# Cell_Phone_Module.net
KiCad netlist of a schematic drawn in Altium Designer
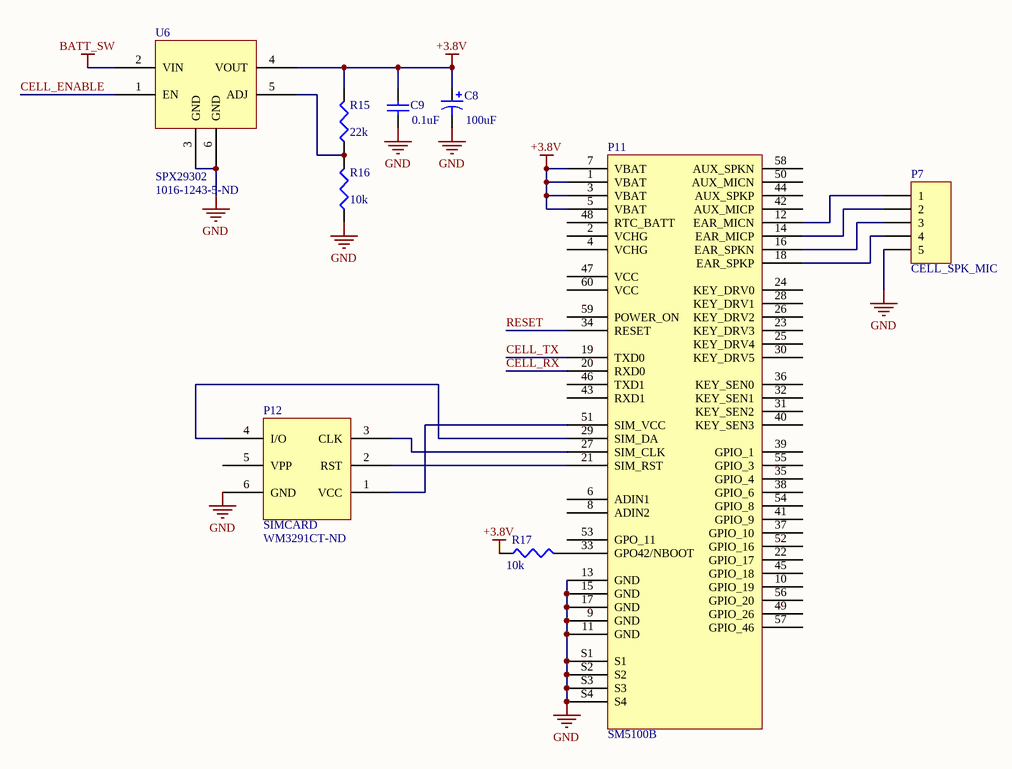
[diagram p0: Cell Phone Module.SchDoc]

(export (version "E")
  (design (tool "Eeschema 10.0.6"))
  (components
    (comp (ref "C8")
      (value "100uF")
      (footprint "TC7343-2917")
      (description "Polarized Capacitor (Surface Mount)")
      (fields (field (name "Comment") "Cap Pol3") (field (name "PUBLISHER") "Altium Limited"))
      (libsource (lib "Miscellaneous Devices") (part "Cap Pol3"))
    )
    (comp (ref "C9")
      (value "0.1uF")
      (footprint "C1206")
      (description "Capacitor (Semiconductor SIM Model)")
      (fields (field (name "Comment") "Cap Semi") (field (name "PUBLISHER") "Altium Limited"))
      (libsource (lib "Miscellaneous Devices") (part "Cap Semi"))
    )
    (comp (ref "P7")
      (value "CELL_SPK_MIC")
      (footprint "2mm JST PH - 5 pin")
      (description "Header, 5-Pin")
      (fields (field (name "PUBLISHER") "Altium Limited"))
      (libsource (lib "Miscellaneous Connectors") (part "Header 5"))
    )
    (comp (ref "P11")
      (value "SM5100B")
      (footprint "SM5100B-60PIN")
      (libsource (lib "Altium Footprints") (part "SM5100B"))
    )
    (comp (ref "P12")
      (value "SIMCARD")
      (footprint "SIMSLOT")
      (fields (field (name "SUPPLIER PART NUMBER 1") "WM3291CT-ND"))
      (libsource (lib "Altium Footprints") (part "SIMHOLDER"))
    )
    (comp (ref "R15")
      (value "22k")
      (footprint "RESC3216M")
      (description "Resistor")
      (fields (field (name "Comment") "Res3") (field (name "PUBLISHER") "Altium Limited"))
      (libsource (lib "Miscellaneous Devices") (part "Res3"))
    )
    (comp (ref "R16")
      (value "10k")
      (footprint "RESC3216M")
      (description "Resistor")
      (fields (field (name "Comment") "Res3") (field (name "PUBLISHER") "Altium Limited"))
      (libsource (lib "Miscellaneous Devices") (part "Res3"))
    )
    (comp (ref "R17")
      (value "10k")
      (footprint "RESC3216M")
      (description "Resistor")
      (fields (field (name "Comment") "Res3") (field (name "PUBLISHER") "Altium Limited"))
      (libsource (lib "Miscellaneous Devices") (part "Res3"))
    )
    (comp (ref "U6")
      (value "SPX29302")
      (footprint "TO170P1520-6N")
      (fields (field (name "SUPPLIER PART NUMBER 1") "1016-1243-5-ND"))
      (libsource (lib "Altium Footprints") (part "SPX29302"))
    )
  )
  (nets
    (net (code "1") (name "+3.8V") (class "Default")
      (node (ref "C8") (pin "1") (pinfunction "1_1") (pintype "passive"))
      (node (ref "C9") (pin "2") (pinfunction "2_2") (pintype "passive"))
      (node (ref "P11") (pin "1") (pinfunction "VBAT_1") (pintype "passive"))
      (node (ref "P11") (pin "3") (pinfunction "VBAT_3") (pintype "passive"))
      (node (ref "P11") (pin "5") (pinfunction "VBAT_5") (pintype "passive"))
      (node (ref "P11") (pin "7") (pinfunction "VBAT_7") (pintype "passive"))
      (node (ref "R15") (pin "2") (pinfunction "2_2") (pintype "passive"))
      (node (ref "R17") (pin "1") (pinfunction "1_1") (pintype "passive"))
      (node (ref "U6") (pin "4") (pinfunction "VOUT_4") (pintype "passive"))
    )
    (net (code "2") (name "/CELL_ENABLE") (class "Default")
      (node (ref "U6") (pin "1") (pinfunction "EN_1") (pintype "passive"))
    )
    (net (code "3") (name "/CELL_RX") (class "Default")
      (node (ref "P11") (pin "20") (pinfunction "RXD0_20") (pintype "passive"))
    )
    (net (code "4") (name "/CELL_TX") (class "Default")
      (node (ref "P11") (pin "19") (pinfunction "TXD0_19") (pintype "passive"))
    )
    (net (code "5") (name "/RESET") (class "Default")
      (node (ref "P11") (pin "34") (pinfunction "RESET_34") (pintype "passive"))
    )
    (net (code "6") (name "BATT_SW") (class "Default")
      (node (ref "U6") (pin "2") (pinfunction "VIN_2") (pintype "passive"))
    )
    (net (code "7") (name "GND") (class "Default")
      (node (ref "C8") (pin "2") (pinfunction "2_2") (pintype "passive"))
      (node (ref "C9") (pin "1") (pinfunction "1_1") (pintype "passive"))
      (node (ref "P11") (pin "11") (pinfunction "GND_11") (pintype "passive"))
      (node (ref "P11") (pin "13") (pinfunction "GND_13") (pintype "passive"))
      (node (ref "P11") (pin "15") (pinfunction "GND_15") (pintype "passive"))
      (node (ref "P11") (pin "17") (pinfunction "GND_17") (pintype "passive"))
      (node (ref "P11") (pin "9") (pinfunction "GND_9") (pintype "passive"))
      (node (ref "P11") (pin "S1") (pinfunction "S1_S1") (pintype "passive"))
      (node (ref "P11") (pin "S2") (pinfunction "S2_S2") (pintype "passive"))
      (node (ref "P11") (pin "S3") (pinfunction "S3_S3") (pintype "passive"))
      (node (ref "P11") (pin "S4") (pinfunction "S4_S4") (pintype "passive"))
      (node (ref "P12") (pin "6") (pinfunction "GND_6") (pintype "passive"))
      (node (ref "P7") (pin "5") (pinfunction "5_5") (pintype "passive"))
      (node (ref "R16") (pin "1") (pinfunction "1_1") (pintype "passive"))
      (node (ref "U6") (pin "3") (pinfunction "GND_3") (pintype "passive"))
      (node (ref "U6") (pin "6") (pinfunction "GND_6") (pintype "passive"))
    )
    (net (code "8") (name "Net-(P11-EAR_MICN)") (class "Default")
      (node (ref "P11") (pin "12") (pinfunction "EAR_MICN_12") (pintype "passive"))
      (node (ref "P7") (pin "1") (pinfunction "1_1") (pintype "passive"))
    )
    (net (code "9") (name "Net-(P11-EAR_MICP)") (class "Default")
      (node (ref "P11") (pin "14") (pinfunction "EAR_MICP_14") (pintype "passive"))
      (node (ref "P7") (pin "2") (pinfunction "2_2") (pintype "passive"))
    )
    (net (code "10") (name "Net-(P11-EAR_SPKN)") (class "Default")
      (node (ref "P11") (pin "16") (pinfunction "EAR_SPKN_16") (pintype "passive"))
      (node (ref "P7") (pin "3") (pinfunction "3_3") (pintype "passive"))
    )
    (net (code "11") (name "Net-(P11-EAR_SPKP)") (class "Default")
      (node (ref "P11") (pin "18") (pinfunction "EAR_SPKP_18") (pintype "passive"))
      (node (ref "P7") (pin "4") (pinfunction "4_4") (pintype "passive"))
    )
    (net (code "12") (name "Net-(P11-GPO42{slash}NBOOT)") (class "Default")
      (node (ref "P11") (pin "33") (pinfunction "GPO42/NBOOT_33") (pintype "passive"))
      (node (ref "R17") (pin "2") (pinfunction "2_2") (pintype "passive"))
    )
    (net (code "13") (name "Net-(P11-SIM_CLK)") (class "Default")
      (node (ref "P11") (pin "27") (pinfunction "SIM_CLK_27") (pintype "passive"))
      (node (ref "P12") (pin "3") (pinfunction "CLK_3") (pintype "passive"))
    )
    (net (code "14") (name "Net-(P11-SIM_DA)") (class "Default")
      (node (ref "P11") (pin "29") (pinfunction "SIM_DA_29") (pintype "passive"))
      (node (ref "P12") (pin "4") (pinfunction "I/O_4") (pintype "passive"))
    )
    (net (code "15") (name "Net-(P11-SIM_RST)") (class "Default")
      (node (ref "P11") (pin "21") (pinfunction "SIM_RST_21") (pintype "passive"))
      (node (ref "P12") (pin "2") (pinfunction "RST_2") (pintype "passive"))
    )
    (net (code "16") (name "Net-(P11-SIM_VCC)") (class "Default")
      (node (ref "P11") (pin "51") (pinfunction "SIM_VCC_51") (pintype "passive"))
      (node (ref "P12") (pin "1") (pinfunction "VCC_1") (pintype "passive"))
    )
    (net (code "17") (name "Net-(U6-ADJ)") (class "Default")
      (node (ref "R15") (pin "1") (pinfunction "1_1") (pintype "passive"))
      (node (ref "R16") (pin "2") (pinfunction "2_2") (pintype "passive"))
      (node (ref "U6") (pin "5") (pinfunction "ADJ_5") (pintype "passive"))
    )
    (net (code "18") (name "unconnected-(P11-ADIN1-Pad6)") (class "Default")
      (node (ref "P11") (pin "6") (pinfunction "ADIN1_6") (pintype "passive"))
    )
    (net (code "19") (name "unconnected-(P11-ADIN2-Pad8)") (class "Default")
      (node (ref "P11") (pin "8") (pinfunction "ADIN2_8") (pintype "passive"))
    )
    (net (code "20") (name "unconnected-(P11-AUX_MICN-Pad50)") (class "Default")
      (node (ref "P11") (pin "50") (pinfunction "AUX_MICN_50") (pintype "passive"))
    )
    (net (code "21") (name "unconnected-(P11-AUX_MICP-Pad42)") (class "Default")
      (node (ref "P11") (pin "42") (pinfunction "AUX_MICP_42") (pintype "passive"))
    )
    (net (code "22") (name "unconnected-(P11-AUX_SPKN-Pad58)") (class "Default")
      (node (ref "P11") (pin "58") (pinfunction "AUX_SPKN_58") (pintype "passive"))
    )
    (net (code "23") (name "unconnected-(P11-AUX_SPKP-Pad44)") (class "Default")
      (node (ref "P11") (pin "44") (pinfunction "AUX_SPKP_44") (pintype "passive"))
    )
    (net (code "24") (name "unconnected-(P11-GPIO_1-Pad39)") (class "Default")
      (node (ref "P11") (pin "39") (pinfunction "GPIO_1_39") (pintype "passive"))
    )
    (net (code "25") (name "unconnected-(P11-GPIO_3-Pad55)") (class "Default")
      (node (ref "P11") (pin "55") (pinfunction "GPIO_3_55") (pintype "passive"))
    )
    (net (code "26") (name "unconnected-(P11-GPIO_4-Pad35)") (class "Default")
      (node (ref "P11") (pin "35") (pinfunction "GPIO_4_35") (pintype "passive"))
    )
    (net (code "27") (name "unconnected-(P11-GPIO_6-Pad38)") (class "Default")
      (node (ref "P11") (pin "38") (pinfunction "GPIO_6_38") (pintype "passive"))
    )
    (net (code "28") (name "unconnected-(P11-GPIO_8-Pad54)") (class "Default")
      (node (ref "P11") (pin "54") (pinfunction "GPIO_8_54") (pintype "passive"))
    )
    (net (code "29") (name "unconnected-(P11-GPIO_9-Pad41)") (class "Default")
      (node (ref "P11") (pin "41") (pinfunction "GPIO_9_41") (pintype "passive"))
    )
    (net (code "30") (name "unconnected-(P11-GPIO_10-Pad37)") (class "Default")
      (node (ref "P11") (pin "37") (pinfunction "GPIO_10_37") (pintype "passive"))
    )
    (net (code "31") (name "unconnected-(P11-GPIO_16-Pad52)") (class "Default")
      (node (ref "P11") (pin "52") (pinfunction "GPIO_16_52") (pintype "passive"))
    )
    (net (code "32") (name "unconnected-(P11-GPIO_17-Pad22)") (class "Default")
      (node (ref "P11") (pin "22") (pinfunction "GPIO_17_22") (pintype "passive"))
    )
    (net (code "33") (name "unconnected-(P11-GPIO_18-Pad45)") (class "Default")
      (node (ref "P11") (pin "45") (pinfunction "GPIO_18_45") (pintype "passive"))
    )
    (net (code "34") (name "unconnected-(P11-GPIO_19-Pad10)") (class "Default")
      (node (ref "P11") (pin "10") (pinfunction "GPIO_19_10") (pintype "passive"))
    )
    (net (code "35") (name "unconnected-(P11-GPIO_20-Pad56)") (class "Default")
      (node (ref "P11") (pin "56") (pinfunction "GPIO_20_56") (pintype "passive"))
    )
    (net (code "36") (name "unconnected-(P11-GPIO_26-Pad49)") (class "Default")
      (node (ref "P11") (pin "49") (pinfunction "GPIO_26_49") (pintype "passive"))
    )
    (net (code "37") (name "unconnected-(P11-GPIO_46-Pad57)") (class "Default")
      (node (ref "P11") (pin "57") (pinfunction "GPIO_46_57") (pintype "passive"))
    )
    (net (code "38") (name "unconnected-(P11-GPO_11-Pad53)") (class "Default")
      (node (ref "P11") (pin "53") (pinfunction "GPO_11_53") (pintype "passive"))
    )
    (net (code "39") (name "unconnected-(P11-KEY_DRV0-Pad24)") (class "Default")
      (node (ref "P11") (pin "24") (pinfunction "KEY_DRV0_24") (pintype "passive"))
    )
    (net (code "40") (name "unconnected-(P11-KEY_DRV1-Pad28)") (class "Default")
      (node (ref "P11") (pin "28") (pinfunction "KEY_DRV1_28") (pintype "passive"))
    )
    (net (code "41") (name "unconnected-(P11-KEY_DRV2-Pad26)") (class "Default")
      (node (ref "P11") (pin "26") (pinfunction "KEY_DRV2_26") (pintype "passive"))
    )
    (net (code "42") (name "unconnected-(P11-KEY_DRV3-Pad23)") (class "Default")
      (node (ref "P11") (pin "23") (pinfunction "KEY_DRV3_23") (pintype "passive"))
    )
    (net (code "43") (name "unconnected-(P11-KEY_DRV4-Pad25)") (class "Default")
      (node (ref "P11") (pin "25") (pinfunction "KEY_DRV4_25") (pintype "passive"))
    )
    (net (code "44") (name "unconnected-(P11-KEY_DRV5-Pad30)") (class "Default")
      (node (ref "P11") (pin "30") (pinfunction "KEY_DRV5_30") (pintype "passive"))
    )
    (net (code "45") (name "unconnected-(P11-KEY_SEN0-Pad36)") (class "Default")
      (node (ref "P11") (pin "36") (pinfunction "KEY_SEN0_36") (pintype "passive"))
    )
    (net (code "46") (name "unconnected-(P11-KEY_SEN1-Pad32)") (class "Default")
      (node (ref "P11") (pin "32") (pinfunction "KEY_SEN1_32") (pintype "passive"))
    )
    (net (code "47") (name "unconnected-(P11-KEY_SEN2-Pad31)") (class "Default")
      (node (ref "P11") (pin "31") (pinfunction "KEY_SEN2_31") (pintype "passive"))
    )
    (net (code "48") (name "unconnected-(P11-KEY_SEN3-Pad40)") (class "Default")
      (node (ref "P11") (pin "40") (pinfunction "KEY_SEN3_40") (pintype "passive"))
    )
    (net (code "49") (name "unconnected-(P11-POWER_ON-Pad59)") (class "Default")
      (node (ref "P11") (pin "59") (pinfunction "POWER_ON_59") (pintype "passive"))
    )
    (net (code "50") (name "unconnected-(P11-RTC_BATT-Pad48)") (class "Default")
      (node (ref "P11") (pin "48") (pinfunction "RTC_BATT_48") (pintype "passive"))
    )
    (net (code "51") (name "unconnected-(P11-RXD1-Pad43)") (class "Default")
      (node (ref "P11") (pin "43") (pinfunction "RXD1_43") (pintype "passive"))
    )
    (net (code "52") (name "unconnected-(P11-TXD1-Pad46)") (class "Default")
      (node (ref "P11") (pin "46") (pinfunction "TXD1_46") (pintype "passive"))
    )
    (net (code "53") (name "unconnected-(P11-VCC-Pad47)") (class "Default")
      (node (ref "P11") (pin "47") (pinfunction "VCC_47") (pintype "passive"))
    )
    (net (code "54") (name "unconnected-(P11-VCC-Pad60)") (class "Default")
      (node (ref "P11") (pin "60") (pinfunction "VCC_60") (pintype "passive"))
    )
    (net (code "55") (name "unconnected-(P11-VCHG-Pad2)") (class "Default")
      (node (ref "P11") (pin "2") (pinfunction "VCHG_2") (pintype "passive"))
    )
    (net (code "56") (name "unconnected-(P11-VCHG-Pad4)") (class "Default")
      (node (ref "P11") (pin "4") (pinfunction "VCHG_4") (pintype "passive"))
    )
    (net (code "57") (name "unconnected-(P12-VPP-Pad5)") (class "Default")
      (node (ref "P12") (pin "5") (pinfunction "VPP_5") (pintype "passive"))
    )
  )
)
